# MCU_SCH.net
KiCad netlist of a schematic drawn in Altium Designer
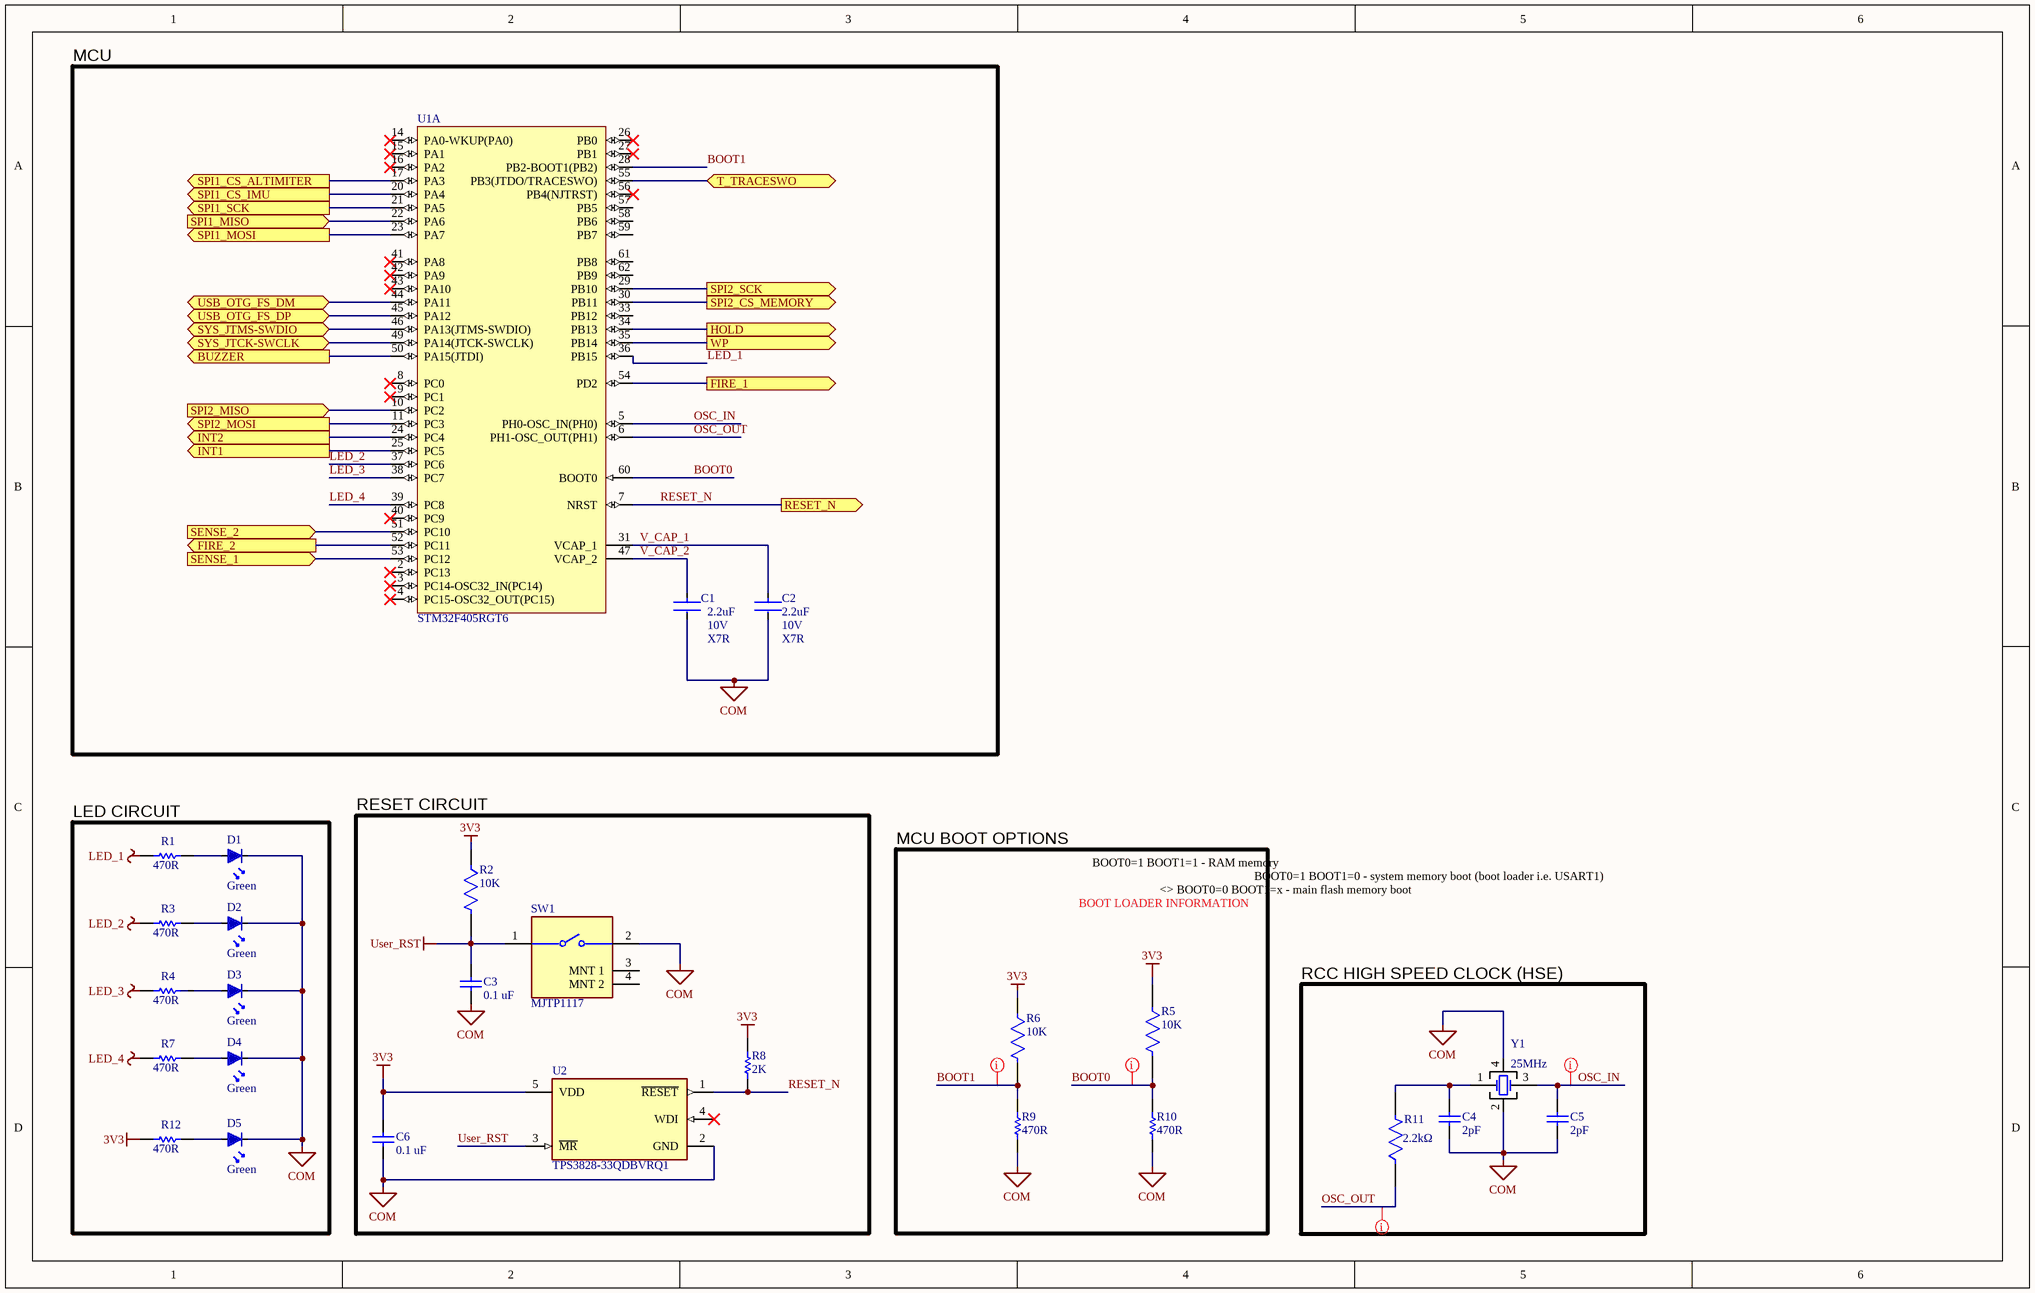
[diagram p0: MCU_SCH.SchDoc]

(export (version "E")
  (design (tool "Eeschema 10.0.6"))
  (components
    (comp (ref "C1")
      (value "LMK107B7225KA-TR")
      (footprint "FP-0603-L_1_6_0_1-W_0_8_0-IPC_C")
      (description "CAP CER 2.2UF 10V X7R 0603")
      (fields
        (field (name "DIELECTRIC") "X7R")
        (field (name "VOLTAGE RATING") "10V")
        (field (name "CAPACITANCE") "2.2uF")
        (field (name "TOLERANCE") "10%")
      )
      (libsource (lib "Altium Content Vault") (part "02cd4be3c70576c341d710602a673aa"))
    )
    (comp (ref "C2")
      (value "LMK107B7225KA-TR")
      (footprint "FP-0603-L_1_6_0_1-W_0_8_0-IPC_C")
      (description "None")
      (fields
        (field (name "DIELECTRIC") "X7R")
        (field (name "VOLTAGE RATING") "10V")
        (field (name "CAPACITANCE") "2.2uF")
        (field (name "TOLERANCE") "10%")
      )
      (libsource (lib "Altium Content Vault") (part "02cd4be3c70576c341d710602a673aa"))
    )
    (comp (ref "C3")
      (value "0.1 uF")
      (footprint "MURA-0603_H_0.9_M")
      (description "CAP, Ceramic, 0.1 uF, 10%, 16 V, 0603, RoHS, Tape and Reel")
      (fields (field (name "MANUFACTURER") "Murata") (field (name "TOLERANCE") "10%"))
      (libsource (lib "Altium Content Vault") (part "CAP-NP-2"))
    )
    (comp (ref "C4")
      (value "2pF")
      (footprint "CAPC1608X92X38LL15T08")
      (description "VJ0603D471KXXAJ CAP CER 2PF 50V C0G/NP0 0603")
      (fields (field (name "MANUFACTURER") "Vitramon") (field (name "PART NUMBER") "VJ0603D471KXXAJ"))
      (libsource (lib "Altium Content Vault") (part "CAP"))
    )
    (comp (ref "C5")
      (value "2pF")
      (footprint "CAPC1608X92X38LL15T08")
      (description "VJ0603D471KXXAJ CAP CER 2PF 50V C0G/NP0 0603")
      (fields (field (name "MANUFACTURER") "Vitramon") (field (name "PART NUMBER") "VJ0603D471KXXAJ"))
      (libsource (lib "Altium Content Vault") (part "CAP"))
    )
    (comp (ref "C6")
      (value "0.1 uF")
      (footprint "MURA-0603_H_0.9_M")
      (fields (field (name "MANUFACTURER") "Murata") (field (name "TOLERANCE") "10%"))
      (libsource (lib "Altium Content Vault") (part "CAP-NP-2"))
    )
    (comp (ref "D1")
      (value "SML-LXR85GC-TR")
      (footprint "D0805")
      (description "LED RA 565NM GREEN WTR CLR SMD 0805")
      (fields (field (name "COLOR") "Green"))
      (libsource (lib "Rockets_2015-2016") (part "SML-LXR85GC-TR"))
    )
    (comp (ref "D2")
      (value "SML-LXR85GC-TR")
      (footprint "D0805")
      (description "LED RA 565NM GREEN WTR CLR SMD 0805")
      (fields (field (name "COLOR") "Green"))
      (libsource (lib "Rockets_2015-2016") (part "SML-LXR85GC-TR"))
    )
    (comp (ref "D3")
      (value "SML-LXR85GC-TR")
      (footprint "D0805")
      (description "LED RA 565NM GREEN WTR CLR SMD 0805")
      (fields (field (name "COLOR") "Green"))
      (libsource (lib "Rockets_2015-2016") (part "SML-LXR85GC-TR"))
    )
    (comp (ref "D4")
      (value "SML-LXR85GC-TR")
      (footprint "D0805")
      (description "LED RA 565NM GREEN WTR CLR SMD 0805")
      (fields (field (name "COLOR") "Green"))
      (libsource (lib "Rockets_2015-2016") (part "SML-LXR85GC-TR"))
    )
    (comp (ref "D5")
      (value "SML-LXR85GC-TR")
      (footprint "D0805")
      (description "LED RA 565NM GREEN WTR CLR SMD 0805")
      (fields (field (name "COLOR") "Green"))
      (libsource (lib "Rockets_2015-2016") (part "SML-LXR85GC-TR"))
    )
    (comp (ref "R1")
      (value "470R")
      (footprint "RESC1608X55X30NL15T15")
      (description "470 Ohm ERJ-3GEYJ471V")
      (fields (field (name "PART NUMBER") "ERJ-3GEYJ471V") (field (name "MANUFACTURER") "Panasonic"))
      (libsource (lib "Altium Content Vault") (part "RES"))
    )
    (comp (ref "R2")
      (value "10K")
      (footprint "FP-ERJ3G-IPC_C")
      (description "RES SMD 10K OHM 5% 1/10W 0603")
      (fields (field (name "TOLERANCE") "5%"))
      (libsource (lib "Altium Content Vault") (part "1029c3af85768c4190bb7ad29bc67b5"))
    )
    (comp (ref "R3")
      (value "470R")
      (footprint "RESC1608X55X30NL15T15")
      (description "ERJ-3GEYJ471V")
      (fields (field (name "MANUFACTURER") "Panasonic"))
      (libsource (lib "Altium Content Vault") (part "RES"))
    )
    (comp (ref "R4")
      (value "470R")
      (footprint "RESC1608X55X30NL15T15")
      (description "ERJ-3GEYJ471V")
      (fields (field (name "MANUFACTURER") "Panasonic"))
      (libsource (lib "Altium Content Vault") (part "RES"))
    )
    (comp (ref "R5")
      (value "10K")
      (footprint "FP-ERJ3G-IPC_C")
      (description "RES SMD 10K OHM 5% 1/10W 0603 ERJ-3GEYJ103V")
      (fields (field (name "TOLERANCE") "5%"))
      (libsource (lib "Altium Content Vault") (part "1029c3af85768c4190bb7ad29bc67b5"))
    )
    (comp (ref "R6")
      (value "10K")
      (footprint "FP-ERJ3G-IPC_C")
      (description "RES SMD 10K OHM 5% 1/10W 0603 ERJ-3GEYJ103V")
      (fields (field (name "TOLERANCE") "5%"))
      (libsource (lib "Altium Content Vault") (part "1029c3af85768c4190bb7ad29bc67b5"))
    )
    (comp (ref "R7")
      (value "470R")
      (footprint "RESC1608X55X30NL15T15")
      (description "ERJ-3GEYJ471V")
      (fields (field (name "MANUFACTURER") "Panasonic"))
      (libsource (lib "Altium Content Vault") (part "RES"))
    )
    (comp (ref "R8")
      (value "2K")
      (footprint "RESC1608X55X30LL15T15")
      (description "ERJ-3GEYJ202V")
      (fields (field (name "MANUFACTURER") "Panasonic"))
      (libsource (lib "Altium Content Vault") (part "RES"))
    )
    (comp (ref "R9")
      (value "470R")
      (footprint "RESC1608X55X30NL15T15")
      (description "ERJ-3GEYJ471V")
      (fields (field (name "MANUFACTURER") "Panasonic"))
      (libsource (lib "Altium Content Vault") (part "RES"))
    )
    (comp (ref "R10")
      (value "470R")
      (footprint "RESC1608X55X30NL15T15")
      (description "ERJ-3GEYJ471V")
      (fields (field (name "MANUFACTURER") "Panasonic"))
      (libsource (lib "Altium Content Vault") (part "RES"))
    )
    (comp (ref "R11")
      (value "ERJ-3GEYJ222V")
      (footprint "FP-ERJ3G-MFG")
      (description "RES SMD 2.2K OHM 5% 1/10W 0603")
      (fields
        (field (name "RESISTANCE") "2.2kΩ")
        (field (name "TOLERANCE") "5%")
        (field (name "MANUFACTURER") "Panasonic")
      )
      (libsource (lib "Altium Content Vault") (part "1029c3af85768c4190bb7ad29bc67b5"))
    )
    (comp (ref "R12")
      (value "470R")
      (footprint "RESC1608X55X30NL15T15")
      (description "ERJ-3GEYJ471V")
      (fields (field (name "MANUFACTURER") "Panasonic"))
      (libsource (lib "Altium Content Vault") (part "RES"))
    )
    (comp (ref "SW1")
      (value "MJTP1117")
      (footprint "FP-MJTP1117-MFG")
      (description "SWITCH TACTILE SPST-NO 0.05A 12V")
      (fields
        (field (name "MANUFACTURER") "Apem Inc.")
        (field (name "OCTOPART") "https://octopart.com/mjtp1117-apem-6499265")
      )
      (libsource (lib "Altium Content Vault") (part "0794c8a440abd5c85081161c1458445"))
    )
    (comp (ref "U1")
      (value "STM32F405RGT6")
      (footprint "STM-LQFP64_M")
      (fields (field (name "MANUFACTURER") "STMicroelectronics"))
      (libsource (lib "Altium Content Vault") (part "MC-ARM-STM32F4X5-SQ64"))
    )
    (comp (ref "U2")
      (value "TPS3828-33QDBVRQ1")
      (footprint "FP-DBV0005A-IPC_C")
      (description "IC SUPERVISOR 1 CHANNEL SOT23-5")
      (libsource (lib "Altium Content Vault") (part "7ec14ae63e89ac1336952769636ba0e"))
    )
    (comp (ref "Y1")
      (value "490-18333-1-ND")
      (footprint "ECS - 4-SMD, No Lead")
      (description "CRYSTAL 25.0000MHZ 6PF SMD")
      (fields (field (name "FREQUENCY") "25MHz"))
      (libsource (lib "Rockets_OSC") (part "XRCGB25M000F0L00R0"))
    )
  )
  (nets
    (net (code "1") (name "/BOOT0") (class "Default")
      (node (ref "R10") (pin "2") (pinfunction "2_2") (pintype "passive"))
      (node (ref "R5") (pin "2") (pinfunction "2_2") (pintype "passive"))
      (node (ref "U1") (pin "60") (pinfunction "BOOT0_60") (pintype "input"))
    )
    (net (code "2") (name "/BOOT1") (class "Default")
      (node (ref "R6") (pin "2") (pinfunction "2_2") (pintype "passive"))
      (node (ref "R9") (pin "2") (pinfunction "2_2") (pintype "passive"))
      (node (ref "U1") (pin "28") (pinfunction "PB2-BOOT1(PB2)_28") (pintype "bidirectional"))
    )
    (net (code "3") (name "/BUZZER") (class "Default")
      (node (ref "U1") (pin "50") (pinfunction "PA15(JTDI)_50") (pintype "bidirectional"))
    )
    (net (code "4") (name "/FIRE_1") (class "Default")
      (node (ref "U1") (pin "54") (pinfunction "PD2_54") (pintype "bidirectional"))
    )
    (net (code "5") (name "/FIRE_2") (class "Default")
      (node (ref "U1") (pin "52") (pinfunction "PC11_52") (pintype "bidirectional"))
    )
    (net (code "6") (name "/HOLD") (class "Default")
      (node (ref "U1") (pin "34") (pinfunction "PB13_34") (pintype "bidirectional"))
    )
    (net (code "7") (name "/INT1") (class "Default")
      (node (ref "U1") (pin "25") (pinfunction "PC5_25") (pintype "bidirectional"))
    )
    (net (code "8") (name "/INT2") (class "Default")
      (node (ref "U1") (pin "24") (pinfunction "PC4_24") (pintype "bidirectional"))
    )
    (net (code "9") (name "/OSC_IN") (class "Default")
      (node (ref "C5") (pin "1") (pinfunction "1_1") (pintype "passive"))
      (node (ref "U1") (pin "5") (pinfunction "PH0-OSC_IN(PH0)_5") (pintype "bidirectional"))
      (node (ref "Y1") (pin "3") (pinfunction "OSC2_3") (pintype "passive"))
    )
    (net (code "10") (name "/OSC_OUT") (class "Default")
      (node (ref "R11") (pin "1") (pinfunction "1_1") (pintype "passive"))
      (node (ref "U1") (pin "6") (pinfunction "PH1-OSC_OUT(PH1)_6") (pintype "bidirectional"))
    )
    (net (code "11") (name "/RESET_N") (class "Default")
      (node (ref "R8") (pin "1") (pinfunction "1_1") (pintype "passive"))
      (node (ref "U1") (pin "7") (pinfunction "NRST_7") (pintype "bidirectional"))
      (node (ref "U2") (pin "1") (pinfunction "~{RESET}_1") (pintype "output"))
    )
    (net (code "12") (name "/SENSE_1") (class "Default")
      (node (ref "U1") (pin "53") (pinfunction "PC12_53") (pintype "bidirectional"))
    )
    (net (code "13") (name "/SENSE_2") (class "Default")
      (node (ref "U1") (pin "51") (pinfunction "PC10_51") (pintype "bidirectional"))
    )
    (net (code "14") (name "/SPI1_CS_ALTIMITER") (class "Default")
      (node (ref "U1") (pin "17") (pinfunction "PA3_17") (pintype "bidirectional"))
    )
    (net (code "15") (name "/SPI1_CS_IMU") (class "Default")
      (node (ref "U1") (pin "20") (pinfunction "PA4_20") (pintype "bidirectional"))
    )
    (net (code "16") (name "/SPI1_MISO") (class "Default")
      (node (ref "U1") (pin "22") (pinfunction "PA6_22") (pintype "bidirectional"))
    )
    (net (code "17") (name "/SPI1_MOSI") (class "Default")
      (node (ref "U1") (pin "23") (pinfunction "PA7_23") (pintype "bidirectional"))
    )
    (net (code "18") (name "/SPI1_SCK") (class "Default")
      (node (ref "U1") (pin "21") (pinfunction "PA5_21") (pintype "bidirectional"))
    )
    (net (code "19") (name "/SPI2_CS_MEMORY") (class "Default")
      (node (ref "U1") (pin "30") (pinfunction "PB11_30") (pintype "bidirectional"))
    )
    (net (code "20") (name "/SPI2_MISO") (class "Default")
      (node (ref "U1") (pin "10") (pinfunction "PC2_10") (pintype "bidirectional"))
    )
    (net (code "21") (name "/SPI2_MOSI") (class "Default")
      (node (ref "U1") (pin "11") (pinfunction "PC3_11") (pintype "bidirectional"))
    )
    (net (code "22") (name "/SPI2_SCK") (class "Default")
      (node (ref "U1") (pin "29") (pinfunction "PB10_29") (pintype "bidirectional"))
    )
    (net (code "23") (name "/SYS_JTCK-SWCLK") (class "Default")
      (node (ref "U1") (pin "49") (pinfunction "PA14(JTCK-SWCLK)_49") (pintype "bidirectional"))
    )
    (net (code "24") (name "/SYS_JTMS-SWDIO") (class "Default")
      (node (ref "U1") (pin "46") (pinfunction "PA13(JTMS-SWDIO)_46") (pintype "bidirectional"))
    )
    (net (code "25") (name "/T_TRACESWO") (class "Default")
      (node (ref "U1") (pin "55") (pinfunction "PB3(JTDO/TRACESWO)_55") (pintype "bidirectional"))
    )
    (net (code "26") (name "/USB_OTG_FS_DM") (class "Default")
      (node (ref "U1") (pin "44") (pinfunction "PA11_44") (pintype "bidirectional"))
    )
    (net (code "27") (name "/USB_OTG_FS_DP") (class "Default")
      (node (ref "U1") (pin "45") (pinfunction "PA12_45") (pintype "bidirectional"))
    )
    (net (code "28") (name "/V_CAP_1") (class "Default")
      (node (ref "C2") (pin "1") (pinfunction "1_1") (pintype "passive"))
      (node (ref "U1") (pin "31") (pinfunction "VCAP_1_31") (pintype "power_in"))
    )
    (net (code "29") (name "/V_CAP_2") (class "Default")
      (node (ref "C1") (pin "1") (pinfunction "1_1") (pintype "passive"))
      (node (ref "U1") (pin "47") (pinfunction "VCAP_2_47") (pintype "power_in"))
    )
    (net (code "30") (name "/WP") (class "Default")
      (node (ref "U1") (pin "35") (pinfunction "PB14_35") (pintype "bidirectional"))
    )
    (net (code "31") (name "3V3") (class "Default")
      (node (ref "C6") (pin "2") (pinfunction "2_2") (pintype "passive"))
      (node (ref "R12") (pin "1") (pinfunction "1_1") (pintype "passive"))
      (node (ref "R2") (pin "1") (pinfunction "1_1") (pintype "passive"))
      (node (ref "R5") (pin "1") (pinfunction "1_1") (pintype "passive"))
      (node (ref "R6") (pin "1") (pinfunction "1_1") (pintype "passive"))
      (node (ref "R8") (pin "2") (pinfunction "2_2") (pintype "passive"))
      (node (ref "U2") (pin "5") (pinfunction "VDD_5") (pintype "power_in"))
    )
    (net (code "32") (name "COM") (class "Default")
      (node (ref "C1") (pin "2") (pinfunction "2_2") (pintype "passive"))
      (node (ref "C2") (pin "2") (pinfunction "2_2") (pintype "passive"))
      (node (ref "C3") (pin "1") (pinfunction "1_1") (pintype "passive"))
      (node (ref "C4") (pin "2") (pinfunction "2_2") (pintype "passive"))
      (node (ref "C5") (pin "2") (pinfunction "2_2") (pintype "passive"))
      (node (ref "C6") (pin "1") (pinfunction "1_1") (pintype "passive"))
      (node (ref "D1") (pin "K") (pinfunction "K_K") (pintype "passive"))
      (node (ref "D2") (pin "K") (pinfunction "K_K") (pintype "passive"))
      (node (ref "D3") (pin "K") (pinfunction "K_K") (pintype "passive"))
      (node (ref "D4") (pin "K") (pinfunction "K_K") (pintype "passive"))
      (node (ref "D5") (pin "K") (pinfunction "K_K") (pintype "passive"))
      (node (ref "R10") (pin "1") (pinfunction "1_1") (pintype "passive"))
      (node (ref "R9") (pin "1") (pinfunction "1_1") (pintype "passive"))
      (node (ref "SW1") (pin "2") (pinfunction "2_2") (pintype "passive"))
      (node (ref "U2") (pin "2") (pinfunction "GND_2") (pintype "power_in"))
      (node (ref "Y1") (pin "2") (pinfunction "4_2") (pintype "passive"))
      (node (ref "Y1") (pin "4") (pinfunction "3_4") (pintype "passive"))
    )
    (net (code "33") (name "LED_1") (class "Default")
      (node (ref "R1") (pin "1") (pinfunction "1_1") (pintype "passive"))
      (node (ref "U1") (pin "36") (pinfunction "PB15_36") (pintype "bidirectional"))
    )
    (net (code "34") (name "LED_2") (class "Default")
      (node (ref "R3") (pin "1") (pinfunction "1_1") (pintype "passive"))
      (node (ref "U1") (pin "37") (pinfunction "PC6_37") (pintype "bidirectional"))
    )
    (net (code "35") (name "LED_3") (class "Default")
      (node (ref "R4") (pin "1") (pinfunction "1_1") (pintype "passive"))
      (node (ref "U1") (pin "38") (pinfunction "PC7_38") (pintype "bidirectional"))
    )
    (net (code "36") (name "LED_4") (class "Default")
      (node (ref "R7") (pin "1") (pinfunction "1_1") (pintype "passive"))
      (node (ref "U1") (pin "39") (pinfunction "PC8_39") (pintype "bidirectional"))
    )
    (net (code "37") (name "Net-(D1-PadA)") (class "Default")
      (node (ref "D1") (pin "A") (pinfunction "A_A") (pintype "passive"))
      (node (ref "R1") (pin "2") (pinfunction "2_2") (pintype "passive"))
    )
    (net (code "38") (name "Net-(D2-PadA)") (class "Default")
      (node (ref "D2") (pin "A") (pinfunction "A_A") (pintype "passive"))
      (node (ref "R3") (pin "2") (pinfunction "2_2") (pintype "passive"))
    )
    (net (code "39") (name "Net-(D3-PadA)") (class "Default")
      (node (ref "D3") (pin "A") (pinfunction "A_A") (pintype "passive"))
      (node (ref "R4") (pin "2") (pinfunction "2_2") (pintype "passive"))
    )
    (net (code "40") (name "Net-(D4-PadA)") (class "Default")
      (node (ref "D4") (pin "A") (pinfunction "A_A") (pintype "passive"))
      (node (ref "R7") (pin "2") (pinfunction "2_2") (pintype "passive"))
    )
    (net (code "41") (name "Net-(D5-PadA)") (class "Default")
      (node (ref "D5") (pin "A") (pinfunction "A_A") (pintype "passive"))
      (node (ref "R12") (pin "2") (pinfunction "2_2") (pintype "passive"))
    )
    (net (code "42") (name "Net-(Y1-OSC1)") (class "Default")
      (node (ref "C4") (pin "1") (pinfunction "1_1") (pintype "passive"))
      (node (ref "R11") (pin "2") (pinfunction "2_2") (pintype "passive"))
      (node (ref "Y1") (pin "1") (pinfunction "OSC1_1") (pintype "passive"))
    )
    (net (code "43") (name "User_RST") (class "Default")
      (node (ref "C3") (pin "2") (pinfunction "2_2") (pintype "passive"))
      (node (ref "R2") (pin "2") (pinfunction "2_2") (pintype "passive"))
      (node (ref "SW1") (pin "1") (pinfunction "1_1") (pintype "passive"))
      (node (ref "U2") (pin "3") (pinfunction "~{MR}_3") (pintype "input"))
    )
    (net (code "44") (name "unconnected-(SW1-MNT_1-Pad3)") (class "Default")
      (node (ref "SW1") (pin "3") (pinfunction "MNT_1_3") (pintype "passive"))
    )
    (net (code "45") (name "unconnected-(SW1-MNT_2-Pad4)") (class "Default")
      (node (ref "SW1") (pin "4") (pinfunction "MNT_2_4") (pintype "passive"))
    )
    (net (code "46") (name "unconnected-(U1A-PA0-WKUP(PA0)-Pad14)") (class "Default")
      (node (ref "U1") (pin "14") (pinfunction "PA0-WKUP(PA0)_14") (pintype "bidirectional+no_connect"))
    )
    (net (code "47") (name "unconnected-(U1A-PA1-Pad15)") (class "Default")
      (node (ref "U1") (pin "15") (pinfunction "PA1_15") (pintype "bidirectional+no_connect"))
    )
    (net (code "48") (name "unconnected-(U1A-PA2-Pad16)") (class "Default")
      (node (ref "U1") (pin "16") (pinfunction "PA2_16") (pintype "bidirectional+no_connect"))
    )
    (net (code "49") (name "unconnected-(U1A-PA8-Pad41)") (class "Default")
      (node (ref "U1") (pin "41") (pinfunction "PA8_41") (pintype "bidirectional+no_connect"))
    )
    (net (code "50") (name "unconnected-(U1A-PA9-Pad42)") (class "Default")
      (node (ref "U1") (pin "42") (pinfunction "PA9_42") (pintype "bidirectional+no_connect"))
    )
    (net (code "51") (name "unconnected-(U1A-PA10-Pad43)") (class "Default")
      (node (ref "U1") (pin "43") (pinfunction "PA10_43") (pintype "bidirectional+no_connect"))
    )
    (net (code "52") (name "unconnected-(U1A-PB0-Pad26)") (class "Default")
      (node (ref "U1") (pin "26") (pinfunction "PB0_26") (pintype "bidirectional+no_connect"))
    )
    (net (code "53") (name "unconnected-(U1A-PB1-Pad27)") (class "Default")
      (node (ref "U1") (pin "27") (pinfunction "PB1_27") (pintype "bidirectional+no_connect"))
    )
    (net (code "54") (name "unconnected-(U1A-PB4(NJTRST)-Pad56)") (class "Default")
      (node (ref "U1") (pin "56") (pinfunction "PB4(NJTRST)_56") (pintype "bidirectional+no_connect"))
    )
    (net (code "55") (name "unconnected-(U1A-PB5-Pad57)") (class "Default")
      (node (ref "U1") (pin "57") (pinfunction "PB5_57") (pintype "bidirectional"))
    )
    (net (code "56") (name "unconnected-(U1A-PB6-Pad58)") (class "Default")
      (node (ref "U1") (pin "58") (pinfunction "PB6_58") (pintype "bidirectional"))
    )
    (net (code "57") (name "unconnected-(U1A-PB7-Pad59)") (class "Default")
      (node (ref "U1") (pin "59") (pinfunction "PB7_59") (pintype "bidirectional"))
    )
    (net (code "58") (name "unconnected-(U1A-PB8-Pad61)") (class "Default")
      (node (ref "U1") (pin "61") (pinfunction "PB8_61") (pintype "bidirectional"))
    )
    (net (code "59") (name "unconnected-(U1A-PB9-Pad62)") (class "Default")
      (node (ref "U1") (pin "62") (pinfunction "PB9_62") (pintype "bidirectional"))
    )
    (net (code "60") (name "unconnected-(U1A-PB12-Pad33)") (class "Default")
      (node (ref "U1") (pin "33") (pinfunction "PB12_33") (pintype "bidirectional"))
    )
    (net (code "61") (name "unconnected-(U1A-PC0-Pad8)") (class "Default")
      (node (ref "U1") (pin "8") (pinfunction "PC0_8") (pintype "bidirectional+no_connect"))
    )
    (net (code "62") (name "unconnected-(U1A-PC1-Pad9)") (class "Default")
      (node (ref "U1") (pin "9") (pinfunction "PC1_9") (pintype "bidirectional+no_connect"))
    )
    (net (code "63") (name "unconnected-(U1A-PC9-Pad40)") (class "Default")
      (node (ref "U1") (pin "40") (pinfunction "PC9_40") (pintype "bidirectional+no_connect"))
    )
    (net (code "64") (name "unconnected-(U1A-PC13-Pad2)") (class "Default")
      (node (ref "U1") (pin "2") (pinfunction "PC13_2") (pintype "bidirectional+no_connect"))
    )
    (net (code "65") (name "unconnected-(U1A-PC14-OSC32_IN(PC14)-Pad3)") (class "Default")
      (node (ref "U1") (pin "3") (pinfunction "PC14-OSC32_IN(PC14)_3") (pintype "bidirectional+no_connect"))
    )
    (net (code "66") (name "unconnected-(U1A-PC15-OSC32_OUT(PC15)-Pad4)") (class "Default")
      (node (ref "U1") (pin "4") (pinfunction "PC15-OSC32_OUT(PC15)_4") (pintype "bidirectional+no_connect"))
    )
    (net (code "67") (name "unconnected-(U2-WDI-Pad4)") (class "Default")
      (node (ref "U2") (pin "4") (pinfunction "WDI_4") (pintype "input+no_connect"))
    )
  )
)
